# 1_Headers.net
KiCad netlist of a schematic drawn in Altium Designer
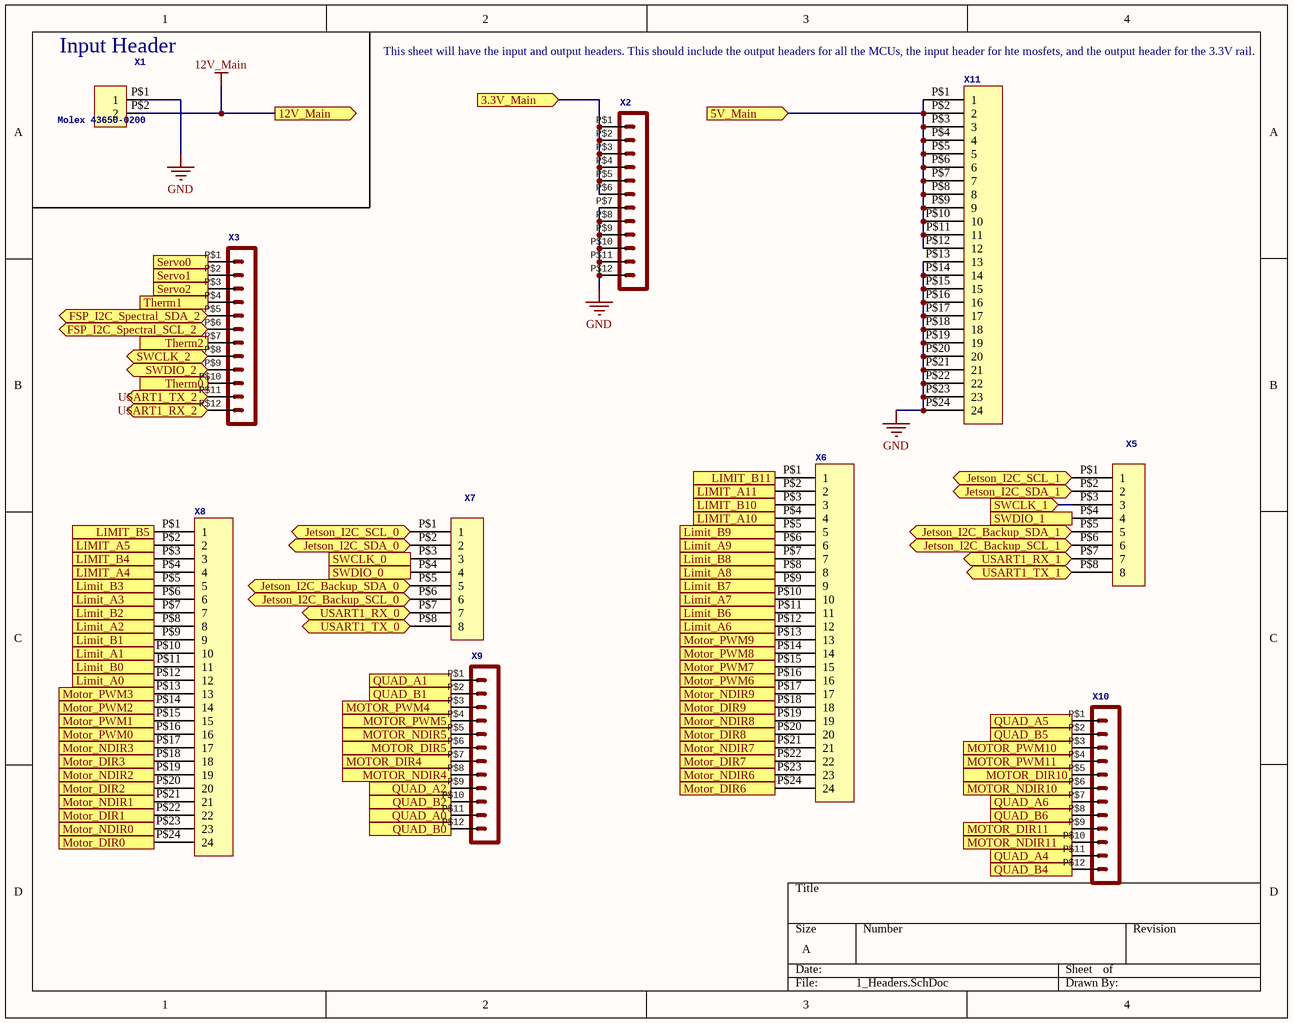
[diagram p0: 1_Headers.SchDoc]

(export (version "E")
  (design (tool "Eeschema 10.0.6"))
  (components
    (comp (ref "X1")
      (value "Molex 43650-0200")
      (footprint "43650-0200")
      (libsource (lib "Molex Microfit") (part "Micro-Fit Molex 2 Pin Right Angle"))
    )
    (comp (ref "X2")
      (value "Molex - Micro-Fit 3.0 Series connector,  3.00mm (0.118\") pitch header, 12 positions.")
      (footprint "43045-1212")
      (libsource (lib "Molex Microfit") (part "HEADER_POS12_?43045-1212"))
    )
    (comp (ref "X3")
      (value "Molex - Micro-Fit 3.0 Series connector,  3.00mm (0.118\") pitch header, 12 positions.")
      (footprint "43045-1212")
      (libsource (lib "Molex Microfit") (part "HEADER_POS12_?43045-1212"))
    )
    (comp (ref "X5")
      (value "Molex 43045-0812")
      (footprint "43045-0812")
      (libsource (lib "Molex Microfit") (part "Micro-Fit Molex 8 Pin 2 Row Vertical"))
    )
    (comp (ref "X6")
      (value "Molex 43045-2412")
      (footprint "43045-2412")
      (libsource (lib "Molex Microfit") (part "Micro-Fit Molex 24 Pin Vertical"))
    )
    (comp (ref "X7")
      (value "Molex 43045-0812")
      (footprint "43045-0812")
      (libsource (lib "Molex Microfit") (part "Micro-Fit Molex 8 Pin 2 Row Vertical"))
    )
    (comp (ref "X8")
      (value "Molex 43045-2412")
      (footprint "43045-2412")
      (libsource (lib "Molex Microfit") (part "Micro-Fit Molex 24 Pin Vertical"))
    )
    (comp (ref "X9")
      (value "Molex - Micro-Fit 3.0 Series connector,  3.00mm (0.118\") pitch header, 12 positions.")
      (footprint "43045-1212")
      (libsource (lib "Molex Microfit") (part "HEADER_POS12_?43045-1212"))
    )
    (comp (ref "X10")
      (value "Molex - Micro-Fit 3.0 Series connector,  3.00mm (0.118\") pitch header, 12 positions.")
      (footprint "43045-1212")
      (libsource (lib "Molex Microfit") (part "HEADER_POS12_?43045-1212"))
    )
    (comp (ref "X11")
      (value "Molex 43045-2412")
      (footprint "43045-2412")
      (libsource (lib "Molex Microfit") (part "Micro-Fit Molex 24 Pin Vertical"))
    )
  )
  (nets
    (net (code "1") (name "/3.3V_Main") (class "Default")
      (node (ref "X2") (pin "P$1") (pinfunction "1_P$1") (pintype "passive"))
      (node (ref "X2") (pin "P$2") (pinfunction "2_P$2") (pintype "passive"))
      (node (ref "X2") (pin "P$3") (pinfunction "3_P$3") (pintype "passive"))
      (node (ref "X2") (pin "P$4") (pinfunction "4_P$4") (pintype "passive"))
      (node (ref "X2") (pin "P$5") (pinfunction "5_P$5") (pintype "passive"))
      (node (ref "X2") (pin "P$6") (pinfunction "6_P$6") (pintype "passive"))
    )
    (net (code "2") (name "/5V_Main") (class "Default")
      (node (ref "X11") (pin "P$1") (pinfunction "1_P$1") (pintype "passive"))
      (node (ref "X11") (pin "P$10") (pinfunction "10_P$10") (pintype "passive"))
      (node (ref "X11") (pin "P$11") (pinfunction "11_P$11") (pintype "passive"))
      (node (ref "X11") (pin "P$12") (pinfunction "12_P$12") (pintype "passive"))
      (node (ref "X11") (pin "P$2") (pinfunction "2_P$2") (pintype "passive"))
      (node (ref "X11") (pin "P$3") (pinfunction "3_P$3") (pintype "passive"))
      (node (ref "X11") (pin "P$4") (pinfunction "4_P$4") (pintype "passive"))
      (node (ref "X11") (pin "P$5") (pinfunction "5_P$5") (pintype "passive"))
      (node (ref "X11") (pin "P$6") (pinfunction "6_P$6") (pintype "passive"))
      (node (ref "X11") (pin "P$7") (pinfunction "7_P$7") (pintype "passive"))
      (node (ref "X11") (pin "P$8") (pinfunction "8_P$8") (pintype "passive"))
      (node (ref "X11") (pin "P$9") (pinfunction "9_P$9") (pintype "passive"))
    )
    (net (code "3") (name "/FSP_I2C_Spectral_SCL_2") (class "Default")
      (node (ref "X3") (pin "P$6") (pinfunction "6_P$6") (pintype "passive"))
    )
    (net (code "4") (name "/FSP_I2C_Spectral_SDA_2") (class "Default")
      (node (ref "X3") (pin "P$5") (pinfunction "5_P$5") (pintype "passive"))
    )
    (net (code "5") (name "/Jetson_I2C_Backup_SCL_0") (class "Default")
      (node (ref "X7") (pin "P$6") (pinfunction "6_P$6") (pintype "passive"))
    )
    (net (code "6") (name "/Jetson_I2C_Backup_SCL_1") (class "Default")
      (node (ref "X5") (pin "P$6") (pinfunction "6_P$6") (pintype "passive"))
    )
    (net (code "7") (name "/Jetson_I2C_Backup_SDA_0") (class "Default")
      (node (ref "X7") (pin "P$5") (pinfunction "5_P$5") (pintype "passive"))
    )
    (net (code "8") (name "/Jetson_I2C_Backup_SDA_1") (class "Default")
      (node (ref "X5") (pin "P$5") (pinfunction "5_P$5") (pintype "passive"))
    )
    (net (code "9") (name "/Jetson_I2C_SCL_0") (class "Default")
      (node (ref "X7") (pin "P$1") (pinfunction "1_P$1") (pintype "passive"))
    )
    (net (code "10") (name "/Jetson_I2C_SCL_1") (class "Default")
      (node (ref "X5") (pin "P$1") (pinfunction "1_P$1") (pintype "passive"))
    )
    (net (code "11") (name "/Jetson_I2C_SDA_0") (class "Default")
      (node (ref "X7") (pin "P$2") (pinfunction "2_P$2") (pintype "passive"))
    )
    (net (code "12") (name "/Jetson_I2C_SDA_1") (class "Default")
      (node (ref "X5") (pin "P$2") (pinfunction "2_P$2") (pintype "passive"))
    )
    (net (code "13") (name "/LIMIT_A4") (class "Default")
      (node (ref "X8") (pin "P$4") (pinfunction "4_P$4") (pintype "passive"))
    )
    (net (code "14") (name "/LIMIT_A5") (class "Default")
      (node (ref "X8") (pin "P$2") (pinfunction "2_P$2") (pintype "passive"))
    )
    (net (code "15") (name "/LIMIT_A10") (class "Default")
      (node (ref "X6") (pin "P$4") (pinfunction "4_P$4") (pintype "passive"))
    )
    (net (code "16") (name "/LIMIT_A11") (class "Default")
      (node (ref "X6") (pin "P$2") (pinfunction "2_P$2") (pintype "passive"))
    )
    (net (code "17") (name "/LIMIT_B4") (class "Default")
      (node (ref "X8") (pin "P$3") (pinfunction "3_P$3") (pintype "passive"))
    )
    (net (code "18") (name "/LIMIT_B5") (class "Default")
      (node (ref "X8") (pin "P$1") (pinfunction "1_P$1") (pintype "passive"))
    )
    (net (code "19") (name "/LIMIT_B10") (class "Default")
      (node (ref "X6") (pin "P$3") (pinfunction "3_P$3") (pintype "passive"))
    )
    (net (code "20") (name "/LIMIT_B11") (class "Default")
      (node (ref "X6") (pin "P$1") (pinfunction "1_P$1") (pintype "passive"))
    )
    (net (code "21") (name "/Limit_A0") (class "Default")
      (node (ref "X8") (pin "P$12") (pinfunction "12_P$12") (pintype "passive"))
    )
    (net (code "22") (name "/Limit_A1") (class "Default")
      (node (ref "X8") (pin "P$10") (pinfunction "10_P$10") (pintype "passive"))
    )
    (net (code "23") (name "/Limit_A2") (class "Default")
      (node (ref "X8") (pin "P$8") (pinfunction "8_P$8") (pintype "passive"))
    )
    (net (code "24") (name "/Limit_A3") (class "Default")
      (node (ref "X8") (pin "P$6") (pinfunction "6_P$6") (pintype "passive"))
    )
    (net (code "25") (name "/Limit_A6") (class "Default")
      (node (ref "X6") (pin "P$12") (pinfunction "12_P$12") (pintype "passive"))
    )
    (net (code "26") (name "/Limit_A7") (class "Default")
      (node (ref "X6") (pin "P$10") (pinfunction "10_P$10") (pintype "passive"))
    )
    (net (code "27") (name "/Limit_A8") (class "Default")
      (node (ref "X6") (pin "P$8") (pinfunction "8_P$8") (pintype "passive"))
    )
    (net (code "28") (name "/Limit_A9") (class "Default")
      (node (ref "X6") (pin "P$6") (pinfunction "6_P$6") (pintype "passive"))
    )
    (net (code "29") (name "/Limit_B0") (class "Default")
      (node (ref "X8") (pin "P$11") (pinfunction "11_P$11") (pintype "passive"))
    )
    (net (code "30") (name "/Limit_B1") (class "Default")
      (node (ref "X8") (pin "P$9") (pinfunction "9_P$9") (pintype "passive"))
    )
    (net (code "31") (name "/Limit_B2") (class "Default")
      (node (ref "X8") (pin "P$7") (pinfunction "7_P$7") (pintype "passive"))
    )
    (net (code "32") (name "/Limit_B3") (class "Default")
      (node (ref "X8") (pin "P$5") (pinfunction "5_P$5") (pintype "passive"))
    )
    (net (code "33") (name "/Limit_B6") (class "Default")
      (node (ref "X6") (pin "P$11") (pinfunction "11_P$11") (pintype "passive"))
    )
    (net (code "34") (name "/Limit_B7") (class "Default")
      (node (ref "X6") (pin "P$9") (pinfunction "9_P$9") (pintype "passive"))
    )
    (net (code "35") (name "/Limit_B8") (class "Default")
      (node (ref "X6") (pin "P$7") (pinfunction "7_P$7") (pintype "passive"))
    )
    (net (code "36") (name "/Limit_B9") (class "Default")
      (node (ref "X6") (pin "P$5") (pinfunction "5_P$5") (pintype "passive"))
    )
    (net (code "37") (name "/MOTOR_DIR4") (class "Default")
      (node (ref "X9") (pin "P$7") (pinfunction "7_P$7") (pintype "passive"))
    )
    (net (code "38") (name "/MOTOR_DIR5") (class "Default")
      (node (ref "X9") (pin "P$6") (pinfunction "6_P$6") (pintype "passive"))
    )
    (net (code "39") (name "/MOTOR_DIR10") (class "Default")
      (node (ref "X10") (pin "P$5") (pinfunction "5_P$5") (pintype "passive"))
    )
    (net (code "40") (name "/MOTOR_DIR11") (class "Default")
      (node (ref "X10") (pin "P$9") (pinfunction "9_P$9") (pintype "passive"))
    )
    (net (code "41") (name "/MOTOR_NDIR4") (class "Default")
      (node (ref "X9") (pin "P$8") (pinfunction "8_P$8") (pintype "passive"))
    )
    (net (code "42") (name "/MOTOR_NDIR5") (class "Default")
      (node (ref "X9") (pin "P$5") (pinfunction "5_P$5") (pintype "passive"))
    )
    (net (code "43") (name "/MOTOR_NDIR10") (class "Default")
      (node (ref "X10") (pin "P$6") (pinfunction "6_P$6") (pintype "passive"))
    )
    (net (code "44") (name "/MOTOR_NDIR11") (class "Default")
      (node (ref "X10") (pin "P$10") (pinfunction "10_P$10") (pintype "passive"))
    )
    (net (code "45") (name "/MOTOR_PWM4") (class "Default")
      (node (ref "X9") (pin "P$3") (pinfunction "3_P$3") (pintype "passive"))
    )
    (net (code "46") (name "/MOTOR_PWM5") (class "Default")
      (node (ref "X9") (pin "P$4") (pinfunction "4_P$4") (pintype "passive"))
    )
    (net (code "47") (name "/MOTOR_PWM10") (class "Default")
      (node (ref "X10") (pin "P$3") (pinfunction "3_P$3") (pintype "passive"))
    )
    (net (code "48") (name "/MOTOR_PWM11") (class "Default")
      (node (ref "X10") (pin "P$4") (pinfunction "4_P$4") (pintype "passive"))
    )
    (net (code "49") (name "/Motor_DIR0") (class "Default")
      (node (ref "X8") (pin "P$24") (pinfunction "24_P$24") (pintype "passive"))
    )
    (net (code "50") (name "/Motor_DIR1") (class "Default")
      (node (ref "X8") (pin "P$22") (pinfunction "22_P$22") (pintype "passive"))
    )
    (net (code "51") (name "/Motor_DIR2") (class "Default")
      (node (ref "X8") (pin "P$20") (pinfunction "20_P$20") (pintype "passive"))
    )
    (net (code "52") (name "/Motor_DIR3") (class "Default")
      (node (ref "X8") (pin "P$18") (pinfunction "18_P$18") (pintype "passive"))
    )
    (net (code "53") (name "/Motor_DIR6") (class "Default")
      (node (ref "X6") (pin "P$24") (pinfunction "24_P$24") (pintype "passive"))
    )
    (net (code "54") (name "/Motor_DIR7") (class "Default")
      (node (ref "X6") (pin "P$22") (pinfunction "22_P$22") (pintype "passive"))
    )
    (net (code "55") (name "/Motor_DIR8") (class "Default")
      (node (ref "X6") (pin "P$20") (pinfunction "20_P$20") (pintype "passive"))
    )
    (net (code "56") (name "/Motor_DIR9") (class "Default")
      (node (ref "X6") (pin "P$18") (pinfunction "18_P$18") (pintype "passive"))
    )
    (net (code "57") (name "/Motor_NDIR0") (class "Default")
      (node (ref "X8") (pin "P$23") (pinfunction "23_P$23") (pintype "passive"))
    )
    (net (code "58") (name "/Motor_NDIR1") (class "Default")
      (node (ref "X8") (pin "P$21") (pinfunction "21_P$21") (pintype "passive"))
    )
    (net (code "59") (name "/Motor_NDIR2") (class "Default")
      (node (ref "X8") (pin "P$19") (pinfunction "19_P$19") (pintype "passive"))
    )
    (net (code "60") (name "/Motor_NDIR3") (class "Default")
      (node (ref "X8") (pin "P$17") (pinfunction "17_P$17") (pintype "passive"))
    )
    (net (code "61") (name "/Motor_NDIR6") (class "Default")
      (node (ref "X6") (pin "P$23") (pinfunction "23_P$23") (pintype "passive"))
    )
    (net (code "62") (name "/Motor_NDIR7") (class "Default")
      (node (ref "X6") (pin "P$21") (pinfunction "21_P$21") (pintype "passive"))
    )
    (net (code "63") (name "/Motor_NDIR8") (class "Default")
      (node (ref "X6") (pin "P$19") (pinfunction "19_P$19") (pintype "passive"))
    )
    (net (code "64") (name "/Motor_NDIR9") (class "Default")
      (node (ref "X6") (pin "P$17") (pinfunction "17_P$17") (pintype "passive"))
    )
    (net (code "65") (name "/Motor_PWM0") (class "Default")
      (node (ref "X8") (pin "P$16") (pinfunction "16_P$16") (pintype "passive"))
    )
    (net (code "66") (name "/Motor_PWM1") (class "Default")
      (node (ref "X8") (pin "P$15") (pinfunction "15_P$15") (pintype "passive"))
    )
    (net (code "67") (name "/Motor_PWM2") (class "Default")
      (node (ref "X8") (pin "P$14") (pinfunction "14_P$14") (pintype "passive"))
    )
    (net (code "68") (name "/Motor_PWM3") (class "Default")
      (node (ref "X8") (pin "P$13") (pinfunction "13_P$13") (pintype "passive"))
    )
    (net (code "69") (name "/Motor_PWM6") (class "Default")
      (node (ref "X6") (pin "P$16") (pinfunction "16_P$16") (pintype "passive"))
    )
    (net (code "70") (name "/Motor_PWM7") (class "Default")
      (node (ref "X6") (pin "P$15") (pinfunction "15_P$15") (pintype "passive"))
    )
    (net (code "71") (name "/Motor_PWM8") (class "Default")
      (node (ref "X6") (pin "P$14") (pinfunction "14_P$14") (pintype "passive"))
    )
    (net (code "72") (name "/Motor_PWM9") (class "Default")
      (node (ref "X6") (pin "P$13") (pinfunction "13_P$13") (pintype "passive"))
    )
    (net (code "73") (name "/QUAD_A0") (class "Default")
      (node (ref "X9") (pin "P$11") (pinfunction "11_P$11") (pintype "passive"))
    )
    (net (code "74") (name "/QUAD_A1") (class "Default")
      (node (ref "X9") (pin "P$1") (pinfunction "1_P$1") (pintype "passive"))
    )
    (net (code "75") (name "/QUAD_A2") (class "Default")
      (node (ref "X9") (pin "P$9") (pinfunction "9_P$9") (pintype "passive"))
    )
    (net (code "76") (name "/QUAD_A4") (class "Default")
      (node (ref "X10") (pin "P$11") (pinfunction "11_P$11") (pintype "passive"))
    )
    (net (code "77") (name "/QUAD_A5") (class "Default")
      (node (ref "X10") (pin "P$1") (pinfunction "1_P$1") (pintype "passive"))
    )
    (net (code "78") (name "/QUAD_A6") (class "Default")
      (node (ref "X10") (pin "P$7") (pinfunction "7_P$7") (pintype "passive"))
    )
    (net (code "79") (name "/QUAD_B0") (class "Default")
      (node (ref "X9") (pin "P$12") (pinfunction "12_P$12") (pintype "passive"))
    )
    (net (code "80") (name "/QUAD_B1") (class "Default")
      (node (ref "X9") (pin "P$2") (pinfunction "2_P$2") (pintype "passive"))
    )
    (net (code "81") (name "/QUAD_B2") (class "Default")
      (node (ref "X9") (pin "P$10") (pinfunction "10_P$10") (pintype "passive"))
    )
    (net (code "82") (name "/QUAD_B4") (class "Default")
      (node (ref "X10") (pin "P$12") (pinfunction "12_P$12") (pintype "passive"))
    )
    (net (code "83") (name "/QUAD_B5") (class "Default")
      (node (ref "X10") (pin "P$2") (pinfunction "2_P$2") (pintype "passive"))
    )
    (net (code "84") (name "/QUAD_B6") (class "Default")
      (node (ref "X10") (pin "P$8") (pinfunction "8_P$8") (pintype "passive"))
    )
    (net (code "85") (name "/SWCLK_0") (class "Default")
      (node (ref "X7") (pin "P$3") (pinfunction "3_P$3") (pintype "passive"))
    )
    (net (code "86") (name "/SWCLK_1") (class "Default")
      (node (ref "X5") (pin "P$3") (pinfunction "3_P$3") (pintype "passive"))
    )
    (net (code "87") (name "/SWCLK_2") (class "Default")
      (node (ref "X3") (pin "P$8") (pinfunction "8_P$8") (pintype "passive"))
    )
    (net (code "88") (name "/SWDIO_0") (class "Default")
      (node (ref "X7") (pin "P$4") (pinfunction "4_P$4") (pintype "passive"))
    )
    (net (code "89") (name "/SWDIO_1") (class "Default")
      (node (ref "X5") (pin "P$4") (pinfunction "4_P$4") (pintype "passive"))
    )
    (net (code "90") (name "/SWDIO_2") (class "Default")
      (node (ref "X3") (pin "P$9") (pinfunction "9_P$9") (pintype "passive"))
    )
    (net (code "91") (name "/Servo0") (class "Default")
      (node (ref "X3") (pin "P$1") (pinfunction "1_P$1") (pintype "passive"))
    )
    (net (code "92") (name "/Servo1") (class "Default")
      (node (ref "X3") (pin "P$2") (pinfunction "2_P$2") (pintype "passive"))
    )
    (net (code "93") (name "/Servo2") (class "Default")
      (node (ref "X3") (pin "P$3") (pinfunction "3_P$3") (pintype "passive"))
    )
    (net (code "94") (name "/Therm0") (class "Default")
      (node (ref "X3") (pin "P$10") (pinfunction "10_P$10") (pintype "passive"))
    )
    (net (code "95") (name "/Therm1") (class "Default")
      (node (ref "X3") (pin "P$4") (pinfunction "4_P$4") (pintype "passive"))
    )
    (net (code "96") (name "/Therm2") (class "Default")
      (node (ref "X3") (pin "P$7") (pinfunction "7_P$7") (pintype "passive"))
    )
    (net (code "97") (name "/USART1_RX_0") (class "Default")
      (node (ref "X7") (pin "P$7") (pinfunction "7_P$7") (pintype "passive"))
    )
    (net (code "98") (name "/USART1_RX_1") (class "Default")
      (node (ref "X5") (pin "P$7") (pinfunction "7_P$7") (pintype "passive"))
    )
    (net (code "99") (name "/USART1_RX_2") (class "Default")
      (node (ref "X3") (pin "P$12") (pinfunction "12_P$12") (pintype "passive"))
    )
    (net (code "100") (name "/USART1_TX_0") (class "Default")
      (node (ref "X7") (pin "P$8") (pinfunction "8_P$8") (pintype "passive"))
    )
    (net (code "101") (name "/USART1_TX_1") (class "Default")
      (node (ref "X5") (pin "P$8") (pinfunction "8_P$8") (pintype "passive"))
    )
    (net (code "102") (name "/USART1_TX_2") (class "Default")
      (node (ref "X3") (pin "P$11") (pinfunction "11_P$11") (pintype "passive"))
    )
    (net (code "103") (name "12V_Main") (class "Default")
      (node (ref "X1") (pin "P$2") (pinfunction "2_P$2") (pintype "passive"))
    )
    (net (code "104") (name "GND") (class "Default")
      (node (ref "X1") (pin "P$1") (pinfunction "1_P$1") (pintype "passive"))
      (node (ref "X11") (pin "P$13") (pinfunction "13_P$13") (pintype "passive"))
      (node (ref "X11") (pin "P$14") (pinfunction "14_P$14") (pintype "passive"))
      (node (ref "X11") (pin "P$15") (pinfunction "15_P$15") (pintype "passive"))
      (node (ref "X11") (pin "P$16") (pinfunction "16_P$16") (pintype "passive"))
      (node (ref "X11") (pin "P$17") (pinfunction "17_P$17") (pintype "passive"))
      (node (ref "X11") (pin "P$18") (pinfunction "18_P$18") (pintype "passive"))
      (node (ref "X11") (pin "P$19") (pinfunction "19_P$19") (pintype "passive"))
      (node (ref "X11") (pin "P$20") (pinfunction "20_P$20") (pintype "passive"))
      (node (ref "X11") (pin "P$21") (pinfunction "21_P$21") (pintype "passive"))
      (node (ref "X11") (pin "P$22") (pinfunction "22_P$22") (pintype "passive"))
      (node (ref "X11") (pin "P$23") (pinfunction "23_P$23") (pintype "passive"))
      (node (ref "X11") (pin "P$24") (pinfunction "24_P$24") (pintype "passive"))
      (node (ref "X2") (pin "P$10") (pinfunction "10_P$10") (pintype "passive"))
      (node (ref "X2") (pin "P$11") (pinfunction "11_P$11") (pintype "passive"))
      (node (ref "X2") (pin "P$12") (pinfunction "12_P$12") (pintype "passive"))
      (node (ref "X2") (pin "P$7") (pinfunction "7_P$7") (pintype "passive"))
      (node (ref "X2") (pin "P$8") (pinfunction "8_P$8") (pintype "passive"))
      (node (ref "X2") (pin "P$9") (pinfunction "9_P$9") (pintype "passive"))
    )
  )
)
